# MZ.net
KiCad netlist of a schematic drawn in Altium Designer
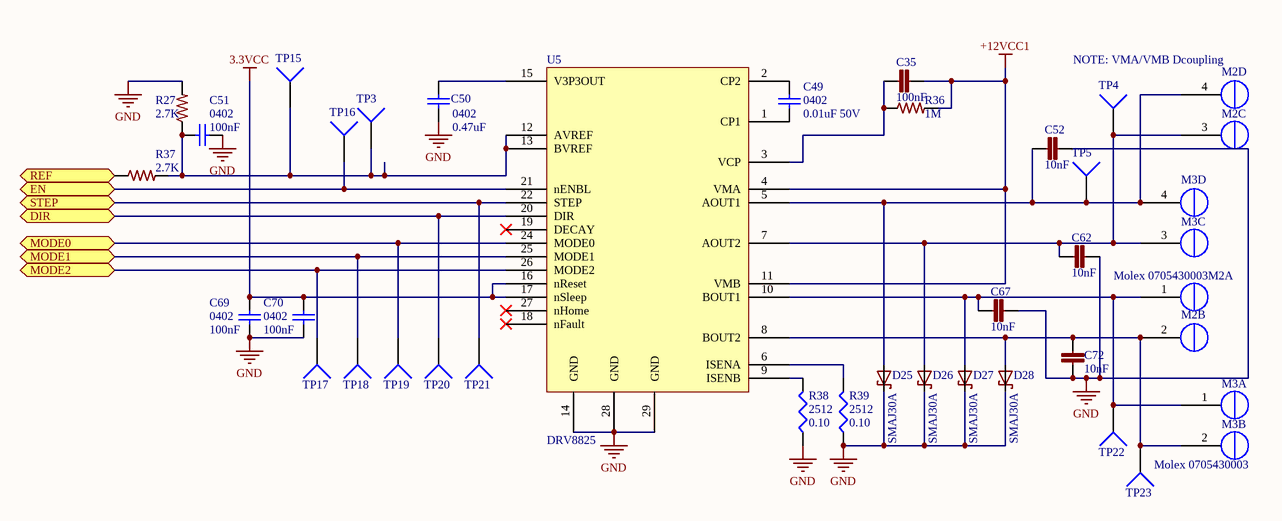
[diagram p0: MZ.SchDoc]

(export (version "E")
  (design (tool "Eeschema 10.0.6"))
  (components
    (comp (ref "C35")
      (value "100nF")
      (footprint "C0603")
      (description "CAP CER 0603 100nF 50V 10% X7R")
      (fields
        (field (name "MANUFACTURERPARTNUMBER") "C0603C104K5RACTU")
        (field (name "PUBLISHER") "UltiMachine")
      )
      (libsource (lib "3Delight") (part "C0603C104K5RACTU"))
    )
    (comp (ref "C49")
      (value "0.01uF 50V")
      (footprint "C0402")
      (description "CAP CER 10000PF 50V X7R 0402")
      (fields
        (field (name "MFR PART #") "GRM155R71H103JA88D")
        (field (name "MFR") "Murata")
        (field (name "PACKAGEREFERENCE") "0402")
        (field (name "PUBLISHER") "Ultimachine")
      )
      (libsource (lib "Tigershark3D") (part "GRM155R71H103JA88D"))
    )
    (comp (ref "C50")
      (value "0.47uF")
      (footprint "C0402")
      (description "0.47uF 6.3v C0402 - GRM155R60J474KE19D")
      (fields
        (field (name "MFR PART #") "GRM155R60J474KE19D")
        (field (name "MFR") "Murata")
        (field (name "PACKAGEREFERENCE") "0402")
        (field (name "PUBLISHER") "Ultimachine")
      )
      (libsource (lib "Tigershark3D") (part "GRM155R60J474KE19D"))
    )
    (comp (ref "C51")
      (value "100nF")
      (footprint "C0402")
      (description "Capacitor (Semiconductor SIM Model)")
      (fields
        (field (name "MFR PART #") "GRM155R71C104KA88D")
        (field (name "MFR") "Murata")
        (field (name "PACKAGEREFERENCE") "0402")
        (field (name "PUBLISHER") "Ultimachine")
      )
      (libsource (lib "Tigershark3D") (part "100nF C0402 - GRM155R71C104KA88D"))
    )
    (comp (ref "C52")
      (value "10nF")
      (footprint "C0603")
      (description "CAP CER 0603 10nF 25V 10% X7R")
      (fields
        (field (name "MANUFACTURERPARTNUMBER") "C1608X7R1E103K080AA")
        (field (name "PUBLISHER") "UltiMachine")
      )
      (libsource (lib "3Delight") (part "C1608X7R1E103K080AA"))
    )
    (comp (ref "C62")
      (value "10nF")
      (footprint "C0603")
      (description "CAP CER 0603 10nF 25V 10% X7R")
      (fields
        (field (name "MANUFACTURERPARTNUMBER") "C1608X7R1E103K080AA")
        (field (name "PUBLISHER") "UltiMachine")
      )
      (libsource (lib "3Delight") (part "C1608X7R1E103K080AA"))
    )
    (comp (ref "C67")
      (value "10nF")
      (footprint "C0603")
      (description "CAP CER 0603 10nF 25V 10% X7R")
      (fields
        (field (name "MANUFACTURERPARTNUMBER") "C1608X7R1E103K080AA")
        (field (name "PUBLISHER") "UltiMachine")
      )
      (libsource (lib "3Delight") (part "C1608X7R1E103K080AA"))
    )
    (comp (ref "C69")
      (value "100nF")
      (footprint "C0402")
      (description "Capacitor (Semiconductor SIM Model)")
      (fields
        (field (name "MFR PART #") "GRM155R71C104KA88D")
        (field (name "MFR") "Murata")
        (field (name "PACKAGEREFERENCE") "0402")
        (field (name "PUBLISHER") "Ultimachine")
      )
      (libsource (lib "Tigershark3D") (part "100nF C0402 - GRM155R71C104KA88D"))
    )
    (comp (ref "C70")
      (value "100nF")
      (footprint "C0402")
      (description "Capacitor (Semiconductor SIM Model)")
      (fields
        (field (name "MFR PART #") "GRM155R71C104KA88D")
        (field (name "MFR") "Murata")
        (field (name "PACKAGEREFERENCE") "0402")
        (field (name "PUBLISHER") "Ultimachine")
      )
      (libsource (lib "Tigershark3D") (part "100nF C0402 - GRM155R71C104KA88D"))
    )
    (comp (ref "C72")
      (value "10nF")
      (footprint "C0603")
      (description "CAP CER 0603 10nF 25V 10% X7R")
      (fields
        (field (name "MANUFACTURERPARTNUMBER") "C1608X7R1E103K080AA")
        (field (name "PUBLISHER") "UltiMachine")
      )
      (libsource (lib "") (part "C1608X7R1E103K080AA_1"))
    )
    (comp (ref "D25")
      (value "SMAJ30A")
      (footprint "SMA-SM")
      (description "DIODE TVS 30V SMA")
      (fields (field (name "PUBLISHER") "UltiMachine"))
      (libsource (lib "Tigershark3D") (part "SMAJ30A"))
    )
    (comp (ref "D26")
      (value "SMAJ30A")
      (footprint "SMA-SM")
      (description "DIODE TVS 30V SMA")
      (fields (field (name "PUBLISHER") "UltiMachine"))
      (libsource (lib "Tigershark3D") (part "SMAJ30A"))
    )
    (comp (ref "D27")
      (value "SMAJ30A")
      (footprint "SMA-SM")
      (description "DIODE TVS 30V SMA")
      (fields (field (name "PUBLISHER") "UltiMachine"))
      (libsource (lib "Tigershark3D") (part "SMAJ30A"))
    )
    (comp (ref "D28")
      (value "SMAJ30A")
      (footprint "SMA-SM")
      (description "DIODE TVS 30V SMA")
      (fields (field (name "PUBLISHER") "UltiMachine"))
      (libsource (lib "Tigershark3D") (part "SMAJ30A"))
    )
    (comp (ref "M2")
      (value "Molex 0705430003")
      (footprint "4POL254")
      (description "Molex 4 Pin Clip Connector")
      (libsource (lib "ZMBo Schematic Library") (part "Molex 0705430003 Alt"))
    )
    (comp (ref "M3")
      (value "Molex 0705430003")
      (footprint "4POL254")
      (description "Molex 4 Pin Clip Connector")
      (libsource (lib "ZMBo Schematic Library") (part "Molex 0705430003 Alt"))
    )
    (comp (ref "R27")
      (value "2.7K")
      (footprint "R0402")
      (description "RES SMD 2.7K OHM 1% 1/10W 0402")
      (fields
        (field (name "MANUFACTURER") "Panasonic")
        (field (name "MANUFACTURERPARTNUMBER") "ERJ2GEJ105X")
        (field (name "PUBLISHER") "Adam")
      )
      (libsource (lib "Tigershark3D") (part "ERJ-2RKF2701X"))
    )
    (comp (ref "R36")
      (value "1M")
      (footprint "R0402")
      (description "RES 0402 1M 100mW 5%")
      (fields (field (name "MANUFACTURERPARTNUMBER") "ERJ2GEJ105X") (field (name "PUBLISHER") "UltiMachine"))
      (libsource (lib "Tigershark3D") (part "ERJ2GEJ105X"))
    )
    (comp (ref "R37")
      (value "2.7K")
      (footprint "R0402")
      (description "RES SMD 2.7K OHM 1% 1/10W 0402")
      (fields
        (field (name "MANUFACTURER") "Panasonic")
        (field (name "MANUFACTURERPARTNUMBER") "ERJ2GEJ105X")
        (field (name "PUBLISHER") "Adam")
      )
      (libsource (lib "Tigershark3D") (part "ERJ-2RKF2701X"))
    )
    (comp (ref "R38")
      (value "2512")
      (footprint "2512R-0.55")
      (description "RES SMD 0.1 OHM 1% 2W 2512")
      (fields (field (name "MFR") "Stackpole ELectronics Inc") (field (name "ALTIUM_VALUE") "0.10"))
      (libsource (lib "Tigershark3D") (part "CSRN2512FTR100"))
    )
    (comp (ref "R39")
      (value "2512")
      (footprint "2512R-0.55")
      (description "RES SMD 0.1 OHM 1% 2W 2512")
      (fields (field (name "MFR") "Stackpole ELectronics Inc") (field (name "ALTIUM_VALUE") "0.10"))
      (libsource (lib "Tigershark3D") (part "CSRN2512FTR100"))
    )
    (comp (ref "TP3")
      (value "TP4")
      (footprint "TP-2")
      (description "Socket")
      (fields (field (name "PUBLISHER") "Altium Limited"))
      (libsource (lib "ZMBo Schematic Library") (part "Socket"))
    )
    (comp (ref "TP4")
      (value "TP4")
      (footprint "TP-2")
      (description "Socket")
      (fields (field (name "PUBLISHER") "Altium Limited"))
      (libsource (lib "ZMBo Schematic Library") (part "Socket"))
    )
    (comp (ref "TP5")
      (value "TP4")
      (footprint "TP-2")
      (description "Socket")
      (fields (field (name "PUBLISHER") "Altium Limited"))
      (libsource (lib "ZMBo Schematic Library") (part "Socket"))
    )
    (comp (ref "TP15")
      (value "TP4")
      (footprint "TP-2")
      (description "Socket")
      (fields (field (name "PUBLISHER") "Altium Limited"))
      (libsource (lib "ZMBo Schematic Library") (part "Socket"))
    )
    (comp (ref "TP16")
      (value "TP4")
      (footprint "TP-2")
      (description "Socket")
      (fields (field (name "PUBLISHER") "Altium Limited"))
      (libsource (lib "ZMBo Schematic Library") (part "Socket"))
    )
    (comp (ref "TP17")
      (value "TP4")
      (footprint "TP-2")
      (description "Socket")
      (fields (field (name "PUBLISHER") "Altium Limited"))
      (libsource (lib "ZMBo Schematic Library") (part "Socket"))
    )
    (comp (ref "TP18")
      (value "TP4")
      (footprint "TP-2")
      (description "Socket")
      (fields (field (name "PUBLISHER") "Altium Limited"))
      (libsource (lib "ZMBo Schematic Library") (part "Socket"))
    )
    (comp (ref "TP19")
      (value "TP4")
      (footprint "TP-2")
      (description "Socket")
      (fields (field (name "PUBLISHER") "Altium Limited"))
      (libsource (lib "ZMBo Schematic Library") (part "Socket"))
    )
    (comp (ref "TP20")
      (value "TP4")
      (footprint "TP-2")
      (description "Socket")
      (fields (field (name "PUBLISHER") "Altium Limited"))
      (libsource (lib "ZMBo Schematic Library") (part "Socket"))
    )
    (comp (ref "TP21")
      (value "TP4")
      (footprint "TP-2")
      (description "Socket")
      (fields (field (name "PUBLISHER") "Altium Limited"))
      (libsource (lib "ZMBo Schematic Library") (part "Socket"))
    )
    (comp (ref "TP22")
      (value "TP4")
      (footprint "TP-2")
      (description "Socket")
      (fields (field (name "PUBLISHER") "Altium Limited"))
      (libsource (lib "ZMBo Schematic Library") (part "Socket"))
    )
    (comp (ref "TP23")
      (value "TP4")
      (footprint "TP-2")
      (description "Socket")
      (fields (field (name "PUBLISHER") "Altium Limited"))
      (libsource (lib "ZMBo Schematic Library") (part "Socket"))
    )
    (comp (ref "U5")
      (value "DRV8825")
      (footprint "DRV8825PWPR")
      (description "DRV8825 Ti Stepper Driver")
      (fields (field (name "PART NUMBER") "DRV8825PWPR") (field (name "VOLTAGE") "8.2-45VDC"))
      (libsource (lib "Tigershark3D") (part "DRV8825"))
    )
  )
  (nets
    (net (code "1") (name "+12VCC1") (class "Default")
      (node (ref "C35") (pin "2") (pinfunction "2_2") (pintype "passive"))
      (node (ref "R36") (pin "2") (pinfunction "2_2") (pintype "passive"))
      (node (ref "U5") (pin "11") (pinfunction "VMB_11") (pintype "passive"))
      (node (ref "U5") (pin "4") (pinfunction "VMA_4") (pintype "passive"))
    )
    (net (code "2") (name "/DIR") (class "Default")
      (node (ref "TP20") (pin "1") (pinfunction "1_1") (pintype "passive"))
      (node (ref "U5") (pin "20") (pinfunction "DIR_20") (pintype "passive"))
    )
    (net (code "3") (name "/EN") (class "Default")
      (node (ref "TP16") (pin "1") (pinfunction "1_1") (pintype "passive"))
      (node (ref "U5") (pin "21") (pinfunction "nENBL_21") (pintype "passive"))
    )
    (net (code "4") (name "/MODE0") (class "Default")
      (node (ref "TP19") (pin "1") (pinfunction "1_1") (pintype "passive"))
      (node (ref "U5") (pin "24") (pinfunction "MODE0_24") (pintype "passive"))
    )
    (net (code "5") (name "/MODE1") (class "Default")
      (node (ref "TP18") (pin "1") (pinfunction "1_1") (pintype "passive"))
      (node (ref "U5") (pin "25") (pinfunction "MODE1_25") (pintype "passive"))
    )
    (net (code "6") (name "/MODE2") (class "Default")
      (node (ref "TP17") (pin "1") (pinfunction "1_1") (pintype "passive"))
      (node (ref "U5") (pin "26") (pinfunction "MODE2_26") (pintype "passive"))
    )
    (net (code "7") (name "/REF") (class "Default")
      (node (ref "R37") (pin "1") (pinfunction "1_1") (pintype "passive"))
    )
    (net (code "8") (name "/STEP") (class "Default")
      (node (ref "TP21") (pin "1") (pinfunction "1_1") (pintype "passive"))
      (node (ref "U5") (pin "22") (pinfunction "STEP_22") (pintype "passive"))
    )
    (net (code "9") (name "3.3VCC") (class "Default")
      (node (ref "C69") (pin "2") (pinfunction "2_2") (pintype "passive"))
      (node (ref "C70") (pin "2") (pinfunction "2_2") (pintype "passive"))
      (node (ref "U5") (pin "16") (pinfunction "nReset_16") (pintype "passive"))
      (node (ref "U5") (pin "17") (pinfunction "nSleep_17") (pintype "passive"))
    )
    (net (code "10") (name "GND") (class "Default")
      (node (ref "C50") (pin "1") (pinfunction "1_1") (pintype "passive"))
      (node (ref "C51") (pin "1") (pinfunction "1_1") (pintype "passive"))
      (node (ref "C52") (pin "2") (pinfunction "2_2") (pintype "passive"))
      (node (ref "C62") (pin "2") (pinfunction "2_2") (pintype "passive"))
      (node (ref "C67") (pin "2") (pinfunction "2_2") (pintype "passive"))
      (node (ref "C69") (pin "1") (pinfunction "1_1") (pintype "passive"))
      (node (ref "C70") (pin "1") (pinfunction "1_1") (pintype "passive"))
      (node (ref "C72") (pin "1") (pinfunction "1_1") (pintype "passive"))
      (node (ref "D25") (pin "C") (pinfunction "C_C") (pintype "passive"))
      (node (ref "D26") (pin "C") (pinfunction "C_C") (pintype "passive"))
      (node (ref "D27") (pin "C") (pinfunction "C_C") (pintype "passive"))
      (node (ref "D28") (pin "C") (pinfunction "C_C") (pintype "passive"))
      (node (ref "R27") (pin "2") (pinfunction "2_2") (pintype "passive"))
      (node (ref "R38") (pin "1") (pinfunction "1_1") (pintype "passive"))
      (node (ref "R39") (pin "1") (pinfunction "1_1") (pintype "passive"))
      (node (ref "U5") (pin "14") (pinfunction "GND_14") (pintype "passive"))
      (node (ref "U5") (pin "28") (pinfunction "GND_28") (pintype "passive"))
      (node (ref "U5") (pin "29") (pinfunction "GND_29") (pintype "passive"))
    )
    (net (code "11") (name "Net-(M2A-OUT2B)") (class "Default")
      (node (ref "C67") (pin "1") (pinfunction "1_1") (pintype "passive"))
      (node (ref "D27") (pin "A") (pinfunction "A_A") (pintype "passive"))
      (node (ref "M2") (pin "1") (pinfunction "OUT2B_1") (pintype "passive"))
      (node (ref "M3") (pin "1") (pinfunction "OUT2B_1") (pintype "passive"))
      (node (ref "TP22") (pin "1") (pinfunction "1_1") (pintype "passive"))
      (node (ref "U5") (pin "10") (pinfunction "BOUT1_10") (pintype "passive"))
    )
    (net (code "12") (name "Net-(M2B-OUT2A)") (class "Default")
      (node (ref "C72") (pin "2") (pinfunction "2_2") (pintype "passive"))
      (node (ref "D28") (pin "A") (pinfunction "A_A") (pintype "passive"))
      (node (ref "M2") (pin "2") (pinfunction "OUT2A_2") (pintype "passive"))
      (node (ref "M3") (pin "2") (pinfunction "OUT2A_2") (pintype "passive"))
      (node (ref "TP23") (pin "1") (pinfunction "1_1") (pintype "passive"))
      (node (ref "U5") (pin "8") (pinfunction "BOUT2_8") (pintype "passive"))
    )
    (net (code "13") (name "Net-(M2C-OUT1A)") (class "Default")
      (node (ref "C62") (pin "1") (pinfunction "1_1") (pintype "passive"))
      (node (ref "D26") (pin "A") (pinfunction "A_A") (pintype "passive"))
      (node (ref "M2") (pin "3") (pinfunction "OUT1A_3") (pintype "passive"))
      (node (ref "M3") (pin "3") (pinfunction "OUT1A_3") (pintype "passive"))
      (node (ref "TP4") (pin "1") (pinfunction "1_1") (pintype "passive"))
      (node (ref "U5") (pin "7") (pinfunction "AOUT2_7") (pintype "passive"))
    )
    (net (code "14") (name "Net-(M2D-OUT1B)") (class "Default")
      (node (ref "C52") (pin "1") (pinfunction "1_1") (pintype "passive"))
      (node (ref "D25") (pin "A") (pinfunction "A_A") (pintype "passive"))
      (node (ref "M2") (pin "4") (pinfunction "OUT1B_4") (pintype "passive"))
      (node (ref "M3") (pin "4") (pinfunction "OUT1B_4") (pintype "passive"))
      (node (ref "TP5") (pin "1") (pinfunction "1_1") (pintype "passive"))
      (node (ref "U5") (pin "5") (pinfunction "AOUT1_5") (pintype "passive"))
    )
    (net (code "15") (name "Net-(U5-AVREF)") (class "Default")
      (node (ref "C51") (pin "2") (pinfunction "2_2") (pintype "passive"))
      (node (ref "R27") (pin "1") (pinfunction "1_1") (pintype "passive"))
      (node (ref "R37") (pin "2") (pinfunction "2_2") (pintype "passive"))
      (node (ref "TP15") (pin "1") (pinfunction "1_1") (pintype "passive"))
      (node (ref "TP3") (pin "1") (pinfunction "1_1") (pintype "passive"))
      (node (ref "U5") (pin "12") (pinfunction "AVREF_12") (pintype "passive"))
      (node (ref "U5") (pin "13") (pinfunction "BVREF_13") (pintype "passive"))
    )
    (net (code "16") (name "Net-(U5-CP1)") (class "Default")
      (node (ref "C49") (pin "1") (pinfunction "1_1") (pintype "passive"))
      (node (ref "U5") (pin "1") (pinfunction "CP1_1") (pintype "passive"))
    )
    (net (code "17") (name "Net-(U5-CP2)") (class "Default")
      (node (ref "C49") (pin "2") (pinfunction "2_2") (pintype "passive"))
      (node (ref "U5") (pin "2") (pinfunction "CP2_2") (pintype "passive"))
    )
    (net (code "18") (name "Net-(U5-ISENA)") (class "Default")
      (node (ref "R39") (pin "2") (pinfunction "2_2") (pintype "passive"))
      (node (ref "U5") (pin "6") (pinfunction "ISENA_6") (pintype "passive"))
    )
    (net (code "19") (name "Net-(U5-ISENB)") (class "Default")
      (node (ref "R38") (pin "2") (pinfunction "2_2") (pintype "passive"))
      (node (ref "U5") (pin "9") (pinfunction "ISENB_9") (pintype "passive"))
    )
    (net (code "20") (name "Net-(U5-V3P3OUT)") (class "Default")
      (node (ref "C50") (pin "2") (pinfunction "2_2") (pintype "passive"))
      (node (ref "U5") (pin "15") (pinfunction "V3P3OUT_15") (pintype "passive"))
    )
    (net (code "21") (name "Net-(U5-VCP)") (class "Default")
      (node (ref "C35") (pin "1") (pinfunction "1_1") (pintype "passive"))
      (node (ref "R36") (pin "1") (pinfunction "1_1") (pintype "passive"))
      (node (ref "U5") (pin "3") (pinfunction "VCP_3") (pintype "passive"))
    )
    (net (code "22") (name "unconnected-(U5-DECAY-Pad19)") (class "Default")
      (node (ref "U5") (pin "19") (pinfunction "DECAY_19") (pintype "passive+no_connect"))
    )
    (net (code "23") (name "unconnected-(U5-NC-Pad23)") (class "Default")
      (node (ref "U5") (pin "23") (pinfunction "NC_23") (pintype "passive"))
    )
    (net (code "24") (name "unconnected-(U5-nFault-Pad18)") (class "Default")
      (node (ref "U5") (pin "18") (pinfunction "nFault_18") (pintype "passive+no_connect"))
    )
    (net (code "25") (name "unconnected-(U5-nHome-Pad27)") (class "Default")
      (node (ref "U5") (pin "27") (pinfunction "nHome_27") (pintype "passive+no_connect"))
    )
  )
)
